# Sheet_1.net
KiCad netlist of a schematic drawn in EasyEDA
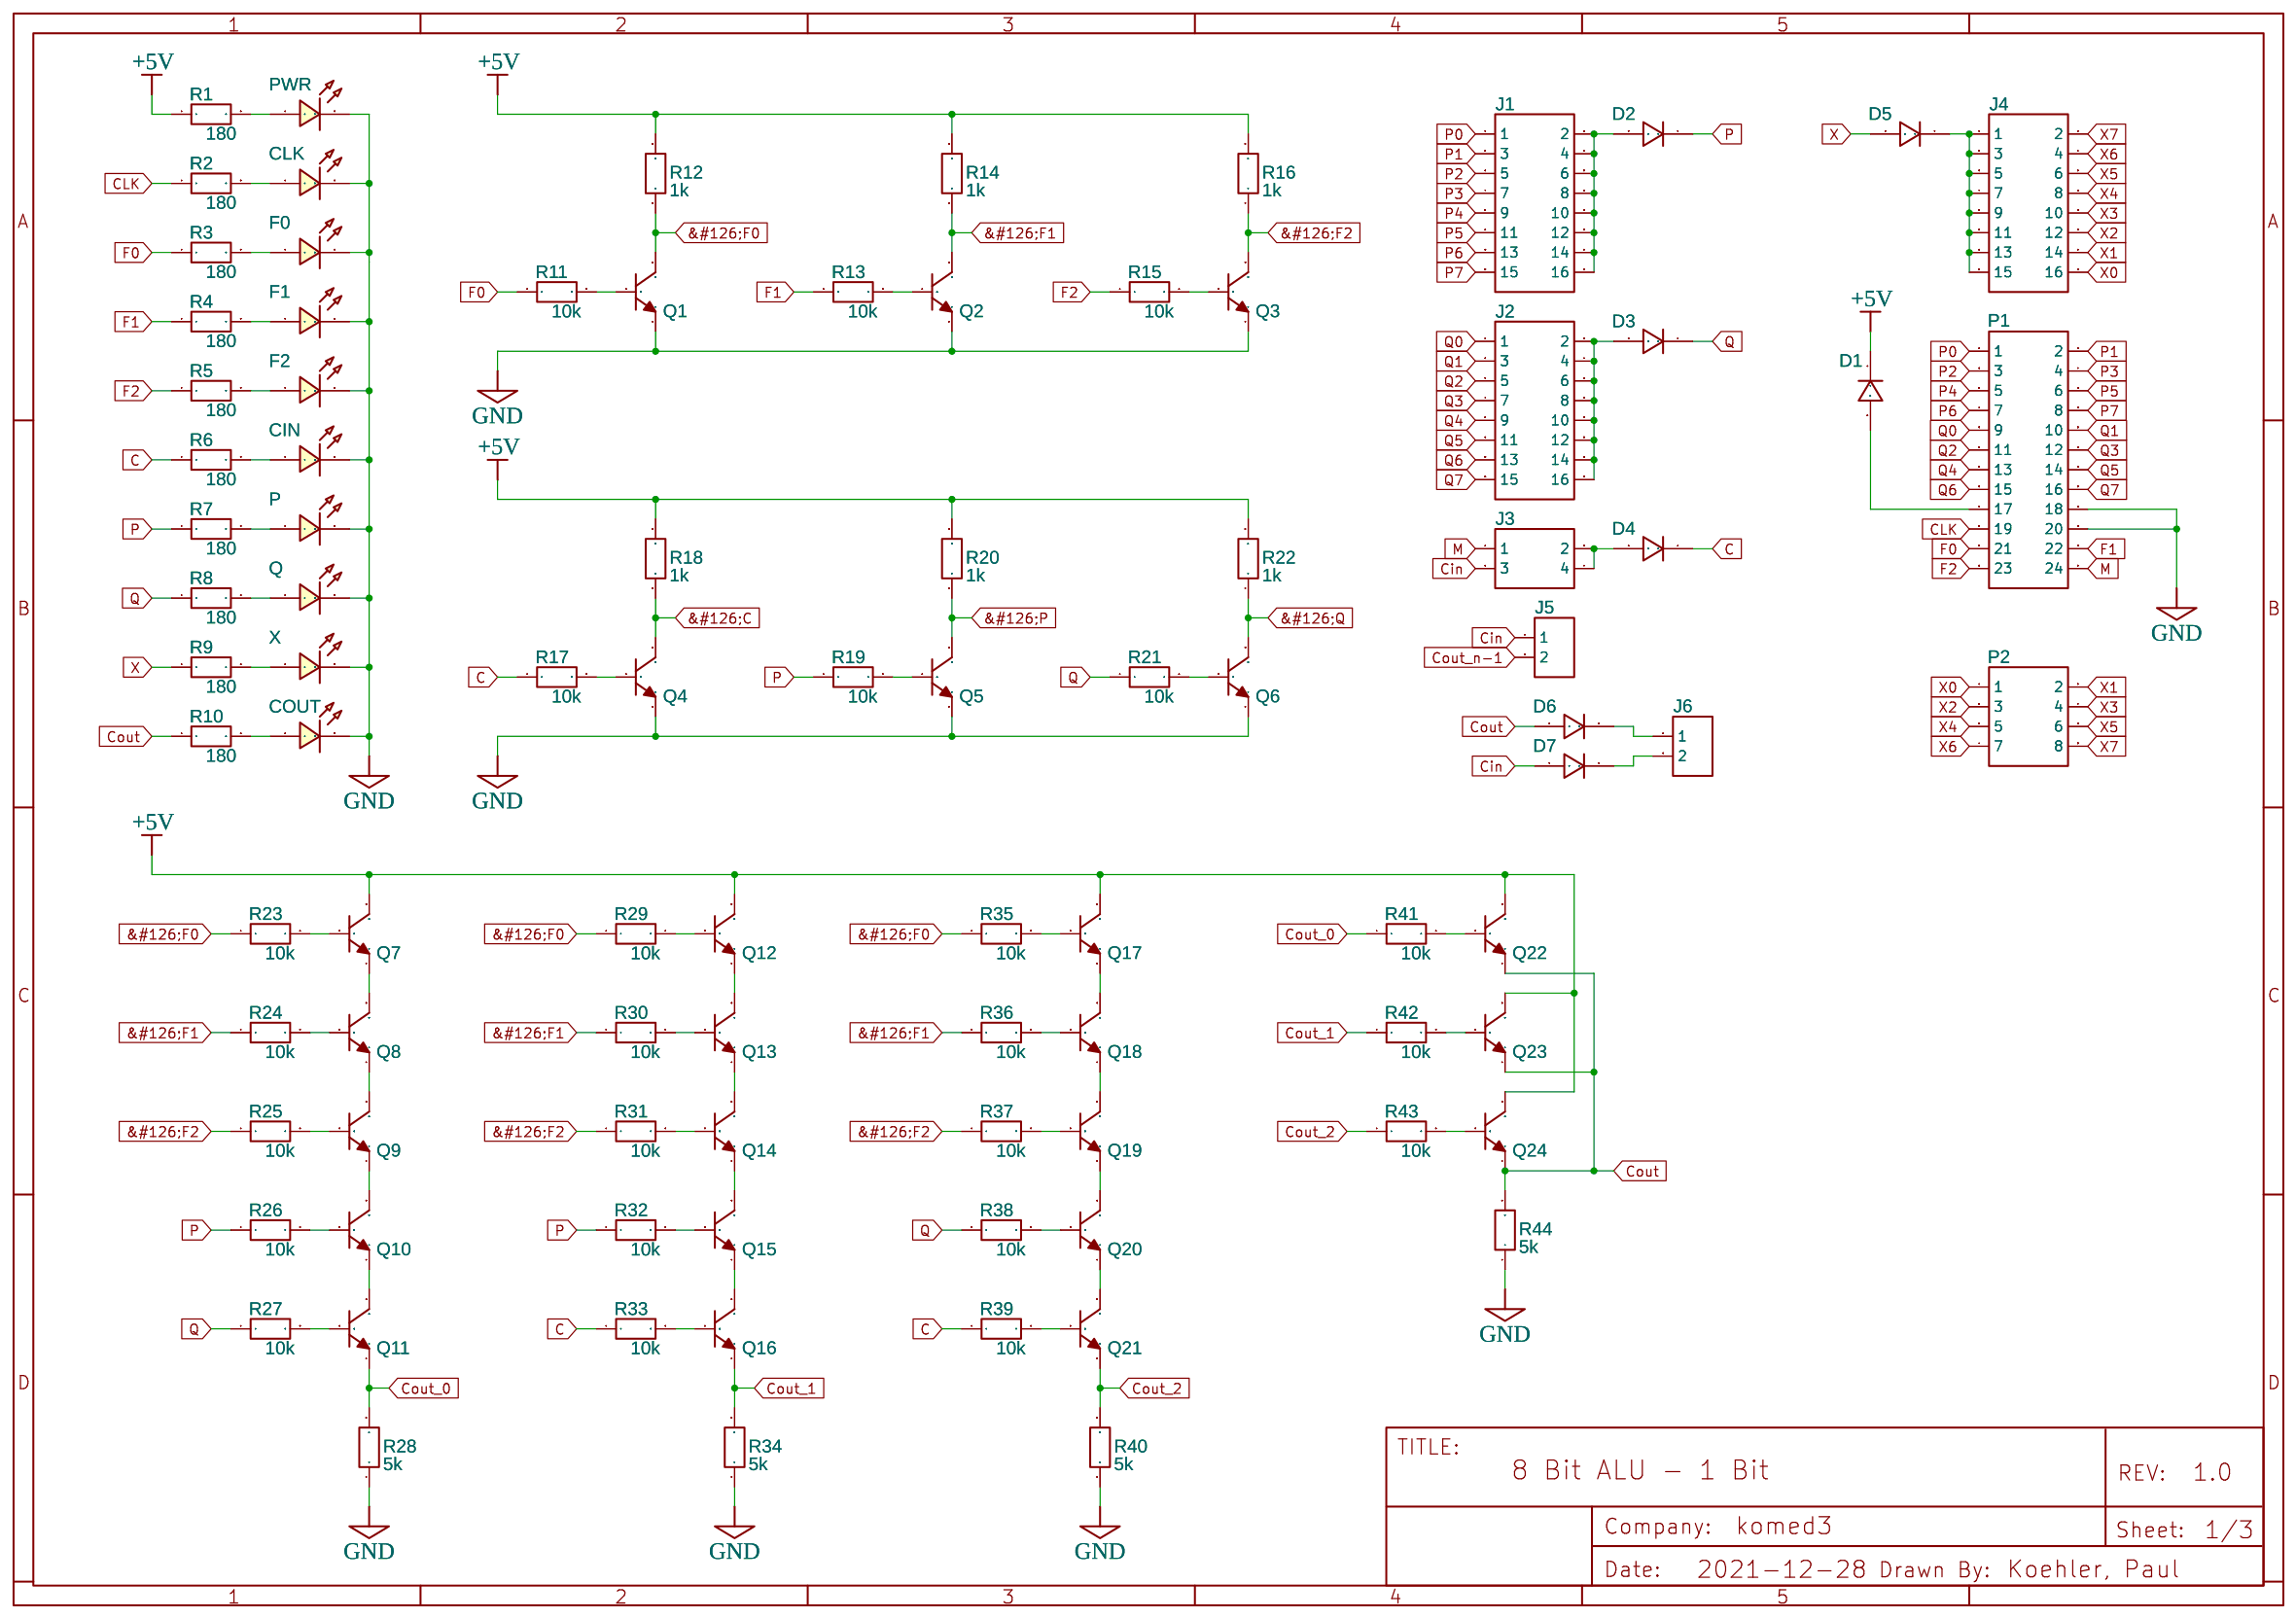
[diagram p0: schematic sheet]

(export (version "E")
  (design (tool "Eeschema 10.0.6"))
  (components
    (comp (ref "CIN")
      (value "LED-TH-5mm_R")
      (fields
        (field (name "BOM_Manufacturer Part") "333-2SURD/S530-A3")
        (field (name "BOM_Supplier Part") "C87271")
      )
      (libsource (lib "") (part "LED-TH-5mm_R_7"))
    )
    (comp (ref "CLK")
      (value "LED-TH-5mm_R")
      (fields
        (field (name "BOM_Manufacturer Part") "333-2SURD/S530-A3")
        (field (name "BOM_Supplier Part") "C87271")
      )
      (libsource (lib "") (part "LED-TH-5mm_R_3"))
    )
    (comp (ref "COUT")
      (value "LED-TH-5mm_R")
      (fields
        (field (name "BOM_Manufacturer Part") "333-2SURD/S530-A3")
        (field (name "BOM_Supplier Part") "C87271")
      )
      (libsource (lib "") (part "LED-TH-5mm_R_5"))
    )
    (comp (ref "D1")
      (value "1N4007")
      (fields (field (name "BOM_Supplier Part") "C106903"))
      (libsource (lib "") (part "1N4007_1"))
    )
    (comp (ref "D2")
      (value "1N4007")
      (fields (field (name "BOM_Supplier Part") "C106903"))
      (libsource (lib "") (part "1N4007"))
    )
    (comp (ref "D3")
      (value "1N4007")
      (fields (field (name "BOM_Supplier Part") "C106903"))
      (libsource (lib "") (part "1N4007"))
    )
    (comp (ref "D4")
      (value "1N4007")
      (fields (field (name "BOM_Supplier Part") "C106903"))
      (libsource (lib "") (part "1N4007"))
    )
    (comp (ref "D5")
      (value "1N4007")
      (fields (field (name "BOM_Supplier Part") "C106903"))
      (libsource (lib "") (part "1N4007"))
    )
    (comp (ref "D6")
      (value "1N4007")
      (fields (field (name "BOM_Supplier Part") "C106903"))
      (libsource (lib "") (part "1N4007"))
    )
    (comp (ref "D7")
      (value "1N4007")
      (fields (field (name "BOM_Supplier Part") "C106903"))
      (libsource (lib "") (part "1N4007"))
    )
    (comp (ref "F0")
      (value "LED-TH-5mm_R")
      (fields
        (field (name "BOM_Manufacturer Part") "333-2SURD/S530-A3")
        (field (name "BOM_Supplier Part") "C87271")
      )
      (libsource (lib "") (part "LED-TH-5mm_R_1"))
    )
    (comp (ref "F1")
      (value "LED-TH-5mm_R")
      (fields
        (field (name "BOM_Manufacturer Part") "333-2SURD/S530-A3")
        (field (name "BOM_Supplier Part") "C87271")
      )
      (libsource (lib "") (part "LED-TH-5mm_R_1"))
    )
    (comp (ref "F2")
      (value "LED-TH-5mm_R")
      (fields
        (field (name "BOM_Manufacturer Part") "333-2SURD/S530-A3")
        (field (name "BOM_Supplier Part") "C87271")
      )
      (libsource (lib "") (part "LED-TH-5mm_R_1"))
    )
    (comp (ref "J1")
      (value "HDR-M-2.54_2x8")
      (fields (field (name "BOM_Supplier Part") "C68234"))
      (libsource (lib "") (part "HDR-M-2.54_2x8"))
    )
    (comp (ref "J2")
      (value "HDR-M-2.54_2x8")
      (fields (field (name "BOM_Supplier Part") "C68234"))
      (libsource (lib "") (part "HDR-M-2.54_2x8"))
    )
    (comp (ref "J3")
      (value "HDR-M-2.54_2x2")
      (fields (field (name "BOM_Supplier Part") "C66690"))
      (libsource (lib "") (part "HDR-M-2.54_2x2"))
    )
    (comp (ref "J4")
      (value "HDR-M-2.54_2x8")
      (fields (field (name "BOM_Supplier Part") "C68234"))
      (libsource (lib "") (part "HDR-M-2.54_2x8"))
    )
    (comp (ref "J5")
      (value "HDR-M-2.54_1x2")
      (fields (field (name "BOM_Supplier Part") "C124375"))
      (libsource (lib "") (part "HDR-M-2.54_1x2"))
    )
    (comp (ref "J6")
      (value "HDR-M-2.54_1x2")
      (fields (field (name "BOM_Supplier Part") "C124375"))
      (libsource (lib "") (part "HDR-M-2.54_1x2"))
    )
    (comp (ref "P")
      (value "LED-TH-5mm_R")
      (fields
        (field (name "BOM_Manufacturer Part") "333-2SURD/S530-A3")
        (field (name "BOM_Supplier Part") "C87271")
      )
      (libsource (lib "") (part "LED-TH-5mm_R_6"))
    )
    (comp (ref "P1")
      (value "HDR-IDC-2.54-2X12P")
      (fields
        (field (name "BOM_Manufacturer Part") "IDC Box 2X12 2.54MM")
        (field (name "BOM_Supplier Part") "C9137")
      )
      (libsource (lib "") (part "HDR-IDC-2.54-2X12P"))
    )
    (comp (ref "P2")
      (value "HDR-IDC-2.54-2X4P")
      (fields
        (field (name "BOM_Manufacturer Part") "IDC Box 2X4 2.54MM")
        (field (name "BOM_Supplier Part") "C9135")
      )
      (libsource (lib "") (part "HDR-IDC-2.54-2X4P"))
    )
    (comp (ref "PWR")
      (value "LED-TH-5mm_R")
      (fields
        (field (name "BOM_Manufacturer Part") "333-2SURD/S530-A3")
        (field (name "BOM_Supplier Part") "C87271")
      )
      (libsource (lib "") (part "LED-TH-5mm_R_4"))
    )
    (comp (ref "Q")
      (value "LED-TH-5mm_R")
      (fields
        (field (name "BOM_Manufacturer Part") "333-2SURD/S530-A3")
        (field (name "BOM_Supplier Part") "C87271")
      )
      (libsource (lib "") (part "LED-TH-5mm_R"))
    )
    (comp (ref "Q1")
      (value "2N3904(TO-92)")
      (fields (field (name "BOM_Manufacturer Part") "2N3904") (field (name "BOM_Supplier Part") "C118538"))
      (libsource (lib "") (part "2N3904(TO-92)"))
    )
    (comp (ref "Q2")
      (value "2N3904(TO-92)")
      (fields (field (name "BOM_Manufacturer Part") "2N3904") (field (name "BOM_Supplier Part") "C118538"))
      (libsource (lib "") (part "2N3904(TO-92)"))
    )
    (comp (ref "Q3")
      (value "2N3904(TO-92)")
      (fields (field (name "BOM_Manufacturer Part") "2N3904") (field (name "BOM_Supplier Part") "C118538"))
      (libsource (lib "") (part "2N3904(TO-92)"))
    )
    (comp (ref "Q4")
      (value "2N3904(TO-92)")
      (fields (field (name "BOM_Manufacturer Part") "2N3904") (field (name "BOM_Supplier Part") "C118538"))
      (libsource (lib "") (part "2N3904(TO-92)"))
    )
    (comp (ref "Q5")
      (value "2N3904(TO-92)")
      (fields (field (name "BOM_Manufacturer Part") "2N3904") (field (name "BOM_Supplier Part") "C118538"))
      (libsource (lib "") (part "2N3904(TO-92)"))
    )
    (comp (ref "Q6")
      (value "2N3904(TO-92)")
      (fields (field (name "BOM_Manufacturer Part") "2N3904") (field (name "BOM_Supplier Part") "C118538"))
      (libsource (lib "") (part "2N3904(TO-92)"))
    )
    (comp (ref "Q7")
      (value "2N3904(TO-92)")
      (fields (field (name "BOM_Manufacturer Part") "2N3904") (field (name "BOM_Supplier Part") "C118538"))
      (libsource (lib "") (part "2N3904(TO-92)"))
    )
    (comp (ref "Q8")
      (value "2N3904(TO-92)")
      (fields (field (name "BOM_Manufacturer Part") "2N3904") (field (name "BOM_Supplier Part") "C118538"))
      (libsource (lib "") (part "2N3904(TO-92)"))
    )
    (comp (ref "Q9")
      (value "2N3904(TO-92)")
      (fields (field (name "BOM_Manufacturer Part") "2N3904") (field (name "BOM_Supplier Part") "C118538"))
      (libsource (lib "") (part "2N3904(TO-92)"))
    )
    (comp (ref "Q10")
      (value "2N3904(TO-92)")
      (fields (field (name "BOM_Manufacturer Part") "2N3904") (field (name "BOM_Supplier Part") "C118538"))
      (libsource (lib "") (part "2N3904(TO-92)"))
    )
    (comp (ref "Q11")
      (value "2N3904(TO-92)")
      (fields (field (name "BOM_Manufacturer Part") "2N3904") (field (name "BOM_Supplier Part") "C118538"))
      (libsource (lib "") (part "2N3904(TO-92)"))
    )
    (comp (ref "Q12")
      (value "2N3904(TO-92)")
      (fields (field (name "BOM_Manufacturer Part") "2N3904") (field (name "BOM_Supplier Part") "C118538"))
      (libsource (lib "") (part "2N3904(TO-92)"))
    )
    (comp (ref "Q13")
      (value "2N3904(TO-92)")
      (fields (field (name "BOM_Manufacturer Part") "2N3904") (field (name "BOM_Supplier Part") "C118538"))
      (libsource (lib "") (part "2N3904(TO-92)"))
    )
    (comp (ref "Q14")
      (value "2N3904(TO-92)")
      (fields (field (name "BOM_Manufacturer Part") "2N3904") (field (name "BOM_Supplier Part") "C118538"))
      (libsource (lib "") (part "2N3904(TO-92)"))
    )
    (comp (ref "Q15")
      (value "2N3904(TO-92)")
      (fields (field (name "BOM_Manufacturer Part") "2N3904") (field (name "BOM_Supplier Part") "C118538"))
      (libsource (lib "") (part "2N3904(TO-92)"))
    )
    (comp (ref "Q16")
      (value "2N3904(TO-92)")
      (fields (field (name "BOM_Manufacturer Part") "2N3904") (field (name "BOM_Supplier Part") "C118538"))
      (libsource (lib "") (part "2N3904(TO-92)"))
    )
    (comp (ref "Q17")
      (value "2N3904(TO-92)")
      (fields (field (name "BOM_Manufacturer Part") "2N3904") (field (name "BOM_Supplier Part") "C118538"))
      (libsource (lib "") (part "2N3904(TO-92)"))
    )
    (comp (ref "Q18")
      (value "2N3904(TO-92)")
      (fields (field (name "BOM_Manufacturer Part") "2N3904") (field (name "BOM_Supplier Part") "C118538"))
      (libsource (lib "") (part "2N3904(TO-92)"))
    )
    (comp (ref "Q19")
      (value "2N3904(TO-92)")
      (fields (field (name "BOM_Manufacturer Part") "2N3904") (field (name "BOM_Supplier Part") "C118538"))
      (libsource (lib "") (part "2N3904(TO-92)"))
    )
    (comp (ref "Q20")
      (value "2N3904(TO-92)")
      (fields (field (name "BOM_Manufacturer Part") "2N3904") (field (name "BOM_Supplier Part") "C118538"))
      (libsource (lib "") (part "2N3904(TO-92)"))
    )
    (comp (ref "Q21")
      (value "2N3904(TO-92)")
      (fields (field (name "BOM_Manufacturer Part") "2N3904") (field (name "BOM_Supplier Part") "C118538"))
      (libsource (lib "") (part "2N3904(TO-92)"))
    )
    (comp (ref "Q22")
      (value "2N3904(TO-92)")
      (fields (field (name "BOM_Manufacturer Part") "2N3904") (field (name "BOM_Supplier Part") "C118538"))
      (libsource (lib "") (part "2N3904(TO-92)"))
    )
    (comp (ref "Q23")
      (value "2N3904(TO-92)")
      (fields (field (name "BOM_Manufacturer Part") "2N3904") (field (name "BOM_Supplier Part") "C118538"))
      (libsource (lib "") (part "2N3904(TO-92)"))
    )
    (comp (ref "Q24")
      (value "2N3904(TO-92)")
      (fields (field (name "BOM_Manufacturer Part") "2N3904") (field (name "BOM_Supplier Part") "C118538"))
      (libsource (lib "") (part "2N3904(TO-92)"))
    )
    (comp (ref "R1") (value "180") (libsource (lib "") (part "R_AXIAL-0.3_EU")))
    (comp (ref "R2") (value "180") (libsource (lib "") (part "R_AXIAL-0.3_EU")))
    (comp (ref "R3") (value "180") (libsource (lib "") (part "R_AXIAL-0.3_EU")))
    (comp (ref "R4") (value "180") (libsource (lib "") (part "R_AXIAL-0.3_EU")))
    (comp (ref "R5") (value "180") (libsource (lib "") (part "R_AXIAL-0.3_EU")))
    (comp (ref "R6") (value "180") (libsource (lib "") (part "R_AXIAL-0.3_EU")))
    (comp (ref "R7") (value "180") (libsource (lib "") (part "R_AXIAL-0.3_EU")))
    (comp (ref "R8") (value "180") (libsource (lib "") (part "R_AXIAL-0.3_EU")))
    (comp (ref "R9") (value "180") (libsource (lib "") (part "R_AXIAL-0.3_EU")))
    (comp (ref "R10") (value "180") (libsource (lib "") (part "R_AXIAL-0.3_EU")))
    (comp (ref "R11") (value "10k") (libsource (lib "") (part "R_AXIAL-0.3_EU")))
    (comp (ref "R12") (value "1k") (libsource (lib "") (part "R_AXIAL-0.3_EU_1")))
    (comp (ref "R13") (value "10k") (libsource (lib "") (part "R_AXIAL-0.3_EU")))
    (comp (ref "R14") (value "1k") (libsource (lib "") (part "R_AXIAL-0.3_EU_1")))
    (comp (ref "R15") (value "10k") (libsource (lib "") (part "R_AXIAL-0.3_EU")))
    (comp (ref "R16") (value "1k") (libsource (lib "") (part "R_AXIAL-0.3_EU_1")))
    (comp (ref "R17") (value "10k") (libsource (lib "") (part "R_AXIAL-0.3_EU")))
    (comp (ref "R18") (value "1k") (libsource (lib "") (part "R_AXIAL-0.3_EU_1")))
    (comp (ref "R19") (value "10k") (libsource (lib "") (part "R_AXIAL-0.3_EU")))
    (comp (ref "R20") (value "1k") (libsource (lib "") (part "R_AXIAL-0.3_EU_1")))
    (comp (ref "R21") (value "10k") (libsource (lib "") (part "R_AXIAL-0.3_EU")))
    (comp (ref "R22") (value "1k") (libsource (lib "") (part "R_AXIAL-0.3_EU_1")))
    (comp (ref "R23") (value "10k") (libsource (lib "") (part "R_AXIAL-0.3_EU")))
    (comp (ref "R24") (value "10k") (libsource (lib "") (part "R_AXIAL-0.3_EU")))
    (comp (ref "R25") (value "10k") (libsource (lib "") (part "R_AXIAL-0.3_EU")))
    (comp (ref "R26") (value "10k") (libsource (lib "") (part "R_AXIAL-0.3_EU")))
    (comp (ref "R27") (value "10k") (libsource (lib "") (part "R_AXIAL-0.3_EU")))
    (comp (ref "R28") (value "5k") (libsource (lib "") (part "R_AXIAL-0.3_EU_1")))
    (comp (ref "R29") (value "10k") (libsource (lib "") (part "R_AXIAL-0.3_EU")))
    (comp (ref "R30") (value "10k") (libsource (lib "") (part "R_AXIAL-0.3_EU")))
    (comp (ref "R31") (value "10k") (libsource (lib "") (part "R_AXIAL-0.3_EU")))
    (comp (ref "R32") (value "10k") (libsource (lib "") (part "R_AXIAL-0.3_EU")))
    (comp (ref "R33") (value "10k") (libsource (lib "") (part "R_AXIAL-0.3_EU")))
    (comp (ref "R34") (value "5k") (libsource (lib "") (part "R_AXIAL-0.3_EU_1")))
    (comp (ref "R35") (value "10k") (libsource (lib "") (part "R_AXIAL-0.3_EU")))
    (comp (ref "R36") (value "10k") (libsource (lib "") (part "R_AXIAL-0.3_EU")))
    (comp (ref "R37") (value "10k") (libsource (lib "") (part "R_AXIAL-0.3_EU")))
    (comp (ref "R38") (value "10k") (libsource (lib "") (part "R_AXIAL-0.3_EU")))
    (comp (ref "R39") (value "10k") (libsource (lib "") (part "R_AXIAL-0.3_EU")))
    (comp (ref "R40") (value "5k") (libsource (lib "") (part "R_AXIAL-0.3_EU_1")))
    (comp (ref "R41") (value "10k") (libsource (lib "") (part "R_AXIAL-0.3_EU")))
    (comp (ref "R42") (value "10k") (libsource (lib "") (part "R_AXIAL-0.3_EU")))
    (comp (ref "R43") (value "10k") (libsource (lib "") (part "R_AXIAL-0.3_EU")))
    (comp (ref "R44") (value "5k") (libsource (lib "") (part "R_AXIAL-0.3_EU_1")))
    (comp (ref "X")
      (value "LED-TH-5mm_R")
      (fields
        (field (name "BOM_Manufacturer Part") "333-2SURD/S530-A3")
        (field (name "BOM_Supplier Part") "C87271")
      )
      (libsource (lib "") (part "LED-TH-5mm_R_2"))
    )
  )
  (nets
    (net (code "1") (name "&#126;C") (class "Default")
      (node (ref "Q4") (pin "3") (pinfunction "C_3") (pintype "unspecified"))
      (node (ref "R18") (pin "1") (pinfunction "1_1") (pintype "unspecified"))
    )
    (net (code "2") (name "&#126;F0") (class "Default")
      (node (ref "Q1") (pin "3") (pinfunction "C_3") (pintype "unspecified"))
      (node (ref "R12") (pin "1") (pinfunction "1_1") (pintype "unspecified"))
      (node (ref "R23") (pin "1") (pinfunction "1_1") (pintype "unspecified"))
      (node (ref "R29") (pin "1") (pinfunction "1_1") (pintype "unspecified"))
      (node (ref "R35") (pin "1") (pinfunction "1_1") (pintype "unspecified"))
    )
    (net (code "3") (name "&#126;F1") (class "Default")
      (node (ref "Q2") (pin "3") (pinfunction "C_3") (pintype "unspecified"))
      (node (ref "R14") (pin "1") (pinfunction "1_1") (pintype "unspecified"))
      (node (ref "R24") (pin "1") (pinfunction "1_1") (pintype "unspecified"))
      (node (ref "R30") (pin "1") (pinfunction "1_1") (pintype "unspecified"))
      (node (ref "R36") (pin "1") (pinfunction "1_1") (pintype "unspecified"))
    )
    (net (code "4") (name "&#126;F2") (class "Default")
      (node (ref "Q3") (pin "3") (pinfunction "C_3") (pintype "unspecified"))
      (node (ref "R16") (pin "1") (pinfunction "1_1") (pintype "unspecified"))
      (node (ref "R25") (pin "1") (pinfunction "1_1") (pintype "unspecified"))
      (node (ref "R31") (pin "1") (pinfunction "1_1") (pintype "unspecified"))
      (node (ref "R37") (pin "1") (pinfunction "1_1") (pintype "unspecified"))
    )
    (net (code "5") (name "&#126;P") (class "Default")
      (node (ref "Q5") (pin "3") (pinfunction "C_3") (pintype "unspecified"))
      (node (ref "R20") (pin "1") (pinfunction "1_1") (pintype "unspecified"))
    )
    (net (code "6") (name "&#126;Q") (class "Default")
      (node (ref "Q6") (pin "3") (pinfunction "C_3") (pintype "unspecified"))
      (node (ref "R22") (pin "1") (pinfunction "1_1") (pintype "unspecified"))
    )
    (net (code "7") (name "+5V") (class "Default")
      (node (ref "D1") (pin "1") (pinfunction "1_1") (pintype "unspecified"))
      (node (ref "Q12") (pin "3") (pinfunction "C_3") (pintype "unspecified"))
      (node (ref "Q17") (pin "3") (pinfunction "C_3") (pintype "unspecified"))
      (node (ref "Q22") (pin "3") (pinfunction "C_3") (pintype "unspecified"))
      (node (ref "Q23") (pin "3") (pinfunction "C_3") (pintype "unspecified"))
      (node (ref "Q24") (pin "3") (pinfunction "C_3") (pintype "unspecified"))
      (node (ref "Q7") (pin "3") (pinfunction "C_3") (pintype "unspecified"))
      (node (ref "R1") (pin "1") (pinfunction "1_1") (pintype "unspecified"))
      (node (ref "R12") (pin "2") (pinfunction "2_2") (pintype "unspecified"))
      (node (ref "R14") (pin "2") (pinfunction "2_2") (pintype "unspecified"))
      (node (ref "R16") (pin "2") (pinfunction "2_2") (pintype "unspecified"))
      (node (ref "R18") (pin "2") (pinfunction "2_2") (pintype "unspecified"))
      (node (ref "R20") (pin "2") (pinfunction "2_2") (pintype "unspecified"))
      (node (ref "R22") (pin "2") (pinfunction "2_2") (pintype "unspecified"))
    )
    (net (code "8") (name "C") (class "Default")
      (node (ref "D4") (pin "1") (pinfunction "1_1") (pintype "unspecified"))
      (node (ref "R17") (pin "1") (pinfunction "1_1") (pintype "unspecified"))
      (node (ref "R33") (pin "1") (pinfunction "1_1") (pintype "unspecified"))
      (node (ref "R39") (pin "1") (pinfunction "1_1") (pintype "unspecified"))
      (node (ref "R6") (pin "1") (pinfunction "1_1") (pintype "unspecified"))
    )
    (net (code "9") (name "CLK") (class "Default")
      (node (ref "P1") (pin "19") (pinfunction "19_19") (pintype "unspecified"))
      (node (ref "R2") (pin "1") (pinfunction "1_1") (pintype "unspecified"))
    )
    (net (code "10") (name "Cin") (class "Default")
      (node (ref "D7") (pin "2") (pinfunction "2_2") (pintype "unspecified"))
      (node (ref "J3") (pin "3") (pinfunction "3_3") (pintype "input"))
      (node (ref "J5") (pin "1") (pinfunction "1_1") (pintype "unspecified"))
    )
    (net (code "11") (name "Cout") (class "Default")
      (node (ref "D6") (pin "2") (pinfunction "2_2") (pintype "unspecified"))
      (node (ref "Q22") (pin "1") (pinfunction "E_1") (pintype "unspecified"))
      (node (ref "Q23") (pin "1") (pinfunction "E_1") (pintype "unspecified"))
      (node (ref "Q24") (pin "1") (pinfunction "E_1") (pintype "unspecified"))
      (node (ref "R10") (pin "1") (pinfunction "1_1") (pintype "unspecified"))
      (node (ref "R44") (pin "2") (pinfunction "2_2") (pintype "unspecified"))
    )
    (net (code "12") (name "Cout_0") (class "Default")
      (node (ref "Q11") (pin "1") (pinfunction "E_1") (pintype "unspecified"))
      (node (ref "R28") (pin "2") (pinfunction "2_2") (pintype "unspecified"))
      (node (ref "R41") (pin "1") (pinfunction "1_1") (pintype "unspecified"))
    )
    (net (code "13") (name "Cout_1") (class "Default")
      (node (ref "Q16") (pin "1") (pinfunction "E_1") (pintype "unspecified"))
      (node (ref "R34") (pin "2") (pinfunction "2_2") (pintype "unspecified"))
      (node (ref "R42") (pin "1") (pinfunction "1_1") (pintype "unspecified"))
    )
    (net (code "14") (name "Cout_2") (class "Default")
      (node (ref "Q21") (pin "1") (pinfunction "E_1") (pintype "unspecified"))
      (node (ref "R40") (pin "2") (pinfunction "2_2") (pintype "unspecified"))
      (node (ref "R43") (pin "1") (pinfunction "1_1") (pintype "unspecified"))
    )
    (net (code "15") (name "Cout_n-1") (class "Default")
      (node (ref "J5") (pin "2") (pinfunction "2_2") (pintype "unspecified"))
    )
    (net (code "16") (name "F0") (class "Default")
      (node (ref "P1") (pin "21") (pinfunction "21_21") (pintype "unspecified"))
      (node (ref "R11") (pin "1") (pinfunction "1_1") (pintype "unspecified"))
      (node (ref "R3") (pin "1") (pinfunction "1_1") (pintype "unspecified"))
    )
    (net (code "17") (name "F1") (class "Default")
      (node (ref "P1") (pin "22") (pinfunction "22_22") (pintype "unspecified"))
      (node (ref "R13") (pin "1") (pinfunction "1_1") (pintype "unspecified"))
      (node (ref "R4") (pin "1") (pinfunction "1_1") (pintype "unspecified"))
    )
    (net (code "18") (name "F2") (class "Default")
      (node (ref "P1") (pin "23") (pinfunction "23_23") (pintype "unspecified"))
      (node (ref "R15") (pin "1") (pinfunction "1_1") (pintype "unspecified"))
      (node (ref "R5") (pin "1") (pinfunction "1_1") (pintype "unspecified"))
    )
    (net (code "19") (name "GND") (class "Default")
      (node (ref "CIN") (pin "2") (pinfunction "2_2") (pintype "unspecified"))
      (node (ref "CLK") (pin "2") (pinfunction "2_2") (pintype "unspecified"))
      (node (ref "COUT") (pin "2") (pinfunction "2_2") (pintype "unspecified"))
      (node (ref "F0") (pin "2") (pinfunction "2_2") (pintype "unspecified"))
      (node (ref "F1") (pin "2") (pinfunction "2_2") (pintype "unspecified"))
      (node (ref "F2") (pin "2") (pinfunction "2_2") (pintype "unspecified"))
      (node (ref "P") (pin "2") (pinfunction "2_2") (pintype "unspecified"))
      (node (ref "P1") (pin "18") (pinfunction "18_18") (pintype "unspecified"))
      (node (ref "P1") (pin "20") (pinfunction "20_20") (pintype "unspecified"))
      (node (ref "PWR") (pin "2") (pinfunction "2_2") (pintype "unspecified"))
      (node (ref "Q") (pin "2") (pinfunction "2_2") (pintype "unspecified"))
      (node (ref "Q1") (pin "1") (pinfunction "E_1") (pintype "unspecified"))
      (node (ref "Q2") (pin "1") (pinfunction "E_1") (pintype "unspecified"))
      (node (ref "Q3") (pin "1") (pinfunction "E_1") (pintype "unspecified"))
      (node (ref "Q4") (pin "1") (pinfunction "E_1") (pintype "unspecified"))
      (node (ref "Q5") (pin "1") (pinfunction "E_1") (pintype "unspecified"))
      (node (ref "Q6") (pin "1") (pinfunction "E_1") (pintype "unspecified"))
      (node (ref "R28") (pin "1") (pinfunction "1_1") (pintype "unspecified"))
      (node (ref "R34") (pin "1") (pinfunction "1_1") (pintype "unspecified"))
      (node (ref "R40") (pin "1") (pinfunction "1_1") (pintype "unspecified"))
      (node (ref "R44") (pin "1") (pinfunction "1_1") (pintype "unspecified"))
      (node (ref "X") (pin "2") (pinfunction "2_2") (pintype "unspecified"))
    )
    (net (code "20") (name "M") (class "Default")
      (node (ref "J3") (pin "1") (pinfunction "1_1") (pintype "input"))
      (node (ref "P1") (pin "24") (pinfunction "24_24") (pintype "unspecified"))
    )
    (net (code "21") (name "Net-(CIN-Pad1)") (class "Default")
      (node (ref "CIN") (pin "1") (pinfunction "1_1") (pintype "unspecified"))
      (node (ref "R6") (pin "2") (pinfunction "2_2") (pintype "unspecified"))
    )
    (net (code "22") (name "Net-(CLK-Pad1)") (class "Default")
      (node (ref "CLK") (pin "1") (pinfunction "1_1") (pintype "unspecified"))
      (node (ref "R2") (pin "2") (pinfunction "2_2") (pintype "unspecified"))
    )
    (net (code "23") (name "Net-(COUT-Pad1)") (class "Default")
      (node (ref "COUT") (pin "1") (pinfunction "1_1") (pintype "unspecified"))
      (node (ref "R10") (pin "2") (pinfunction "2_2") (pintype "unspecified"))
    )
    (net (code "24") (name "Net-(D1-Pad2)") (class "Default")
      (node (ref "D1") (pin "2") (pinfunction "2_2") (pintype "unspecified"))
      (node (ref "P1") (pin "17") (pinfunction "17_17") (pintype "unspecified"))
    )
    (net (code "25") (name "Net-(D2-Pad2)") (class "Default")
      (node (ref "D2") (pin "2") (pinfunction "2_2") (pintype "unspecified"))
      (node (ref "J1") (pin "10") (pinfunction "10_10") (pintype "input"))
      (node (ref "J1") (pin "12") (pinfunction "12_12") (pintype "input"))
      (node (ref "J1") (pin "14") (pinfunction "14_14") (pintype "input"))
      (node (ref "J1") (pin "16") (pinfunction "16_16") (pintype "input"))
      (node (ref "J1") (pin "2") (pinfunction "2_2") (pintype "input"))
      (node (ref "J1") (pin "4") (pinfunction "4_4") (pintype "input"))
      (node (ref "J1") (pin "6") (pinfunction "6_6") (pintype "input"))
      (node (ref "J1") (pin "8") (pinfunction "8_8") (pintype "input"))
    )
    (net (code "26") (name "Net-(D3-Pad2)") (class "Default")
      (node (ref "D3") (pin "2") (pinfunction "2_2") (pintype "unspecified"))
      (node (ref "J2") (pin "10") (pinfunction "10_10") (pintype "input"))
      (node (ref "J2") (pin "12") (pinfunction "12_12") (pintype "input"))
      (node (ref "J2") (pin "14") (pinfunction "14_14") (pintype "input"))
      (node (ref "J2") (pin "16") (pinfunction "16_16") (pintype "input"))
      (node (ref "J2") (pin "2") (pinfunction "2_2") (pintype "input"))
      (node (ref "J2") (pin "4") (pinfunction "4_4") (pintype "input"))
      (node (ref "J2") (pin "6") (pinfunction "6_6") (pintype "input"))
      (node (ref "J2") (pin "8") (pinfunction "8_8") (pintype "input"))
    )
    (net (code "27") (name "Net-(D4-Pad2)") (class "Default")
      (node (ref "D4") (pin "2") (pinfunction "2_2") (pintype "unspecified"))
      (node (ref "J3") (pin "2") (pinfunction "2_2") (pintype "input"))
      (node (ref "J3") (pin "4") (pinfunction "4_4") (pintype "input"))
    )
    (net (code "28") (name "Net-(D5-Pad1)") (class "Default")
      (node (ref "D5") (pin "1") (pinfunction "1_1") (pintype "unspecified"))
      (node (ref "J4") (pin "1") (pinfunction "1_1") (pintype "input"))
      (node (ref "J4") (pin "11") (pinfunction "11_11") (pintype "input"))
      (node (ref "J4") (pin "13") (pinfunction "13_13") (pintype "input"))
      (node (ref "J4") (pin "15") (pinfunction "15_15") (pintype "input"))
      (node (ref "J4") (pin "3") (pinfunction "3_3") (pintype "input"))
      (node (ref "J4") (pin "5") (pinfunction "5_5") (pintype "input"))
      (node (ref "J4") (pin "7") (pinfunction "7_7") (pintype "input"))
      (node (ref "J4") (pin "9") (pinfunction "9_9") (pintype "input"))
    )
    (net (code "29") (name "Net-(D6-Pad1)") (class "Default")
      (node (ref "D6") (pin "1") (pinfunction "1_1") (pintype "unspecified"))
      (node (ref "J6") (pin "1") (pinfunction "1_1") (pintype "unspecified"))
    )
    (net (code "30") (name "Net-(D7-Pad1)") (class "Default")
      (node (ref "D7") (pin "1") (pinfunction "1_1") (pintype "unspecified"))
      (node (ref "J6") (pin "2") (pinfunction "2_2") (pintype "unspecified"))
    )
    (net (code "31") (name "Net-(F0-Pad1)") (class "Default")
      (node (ref "F0") (pin "1") (pinfunction "1_1") (pintype "unspecified"))
      (node (ref "R3") (pin "2") (pinfunction "2_2") (pintype "unspecified"))
    )
    (net (code "32") (name "Net-(F1-Pad1)") (class "Default")
      (node (ref "F1") (pin "1") (pinfunction "1_1") (pintype "unspecified"))
      (node (ref "R4") (pin "2") (pinfunction "2_2") (pintype "unspecified"))
    )
    (net (code "33") (name "Net-(F2-Pad1)") (class "Default")
      (node (ref "F2") (pin "1") (pinfunction "1_1") (pintype "unspecified"))
      (node (ref "R5") (pin "2") (pinfunction "2_2") (pintype "unspecified"))
    )
    (net (code "34") (name "Net-(P-Pad1)") (class "Default")
      (node (ref "P") (pin "1") (pinfunction "1_1") (pintype "unspecified"))
      (node (ref "R7") (pin "2") (pinfunction "2_2") (pintype "unspecified"))
    )
    (net (code "35") (name "Net-(PWR-Pad1)") (class "Default")
      (node (ref "PWR") (pin "1") (pinfunction "1_1") (pintype "unspecified"))
      (node (ref "R1") (pin "2") (pinfunction "2_2") (pintype "unspecified"))
    )
    (net (code "36") (name "Net-(Q-Pad1)") (class "Default")
      (node (ref "Q") (pin "1") (pinfunction "1_1") (pintype "unspecified"))
      (node (ref "R8") (pin "2") (pinfunction "2_2") (pintype "unspecified"))
    )
    (net (code "37") (name "Net-(Q1-B)") (class "Default")
      (node (ref "Q1") (pin "2") (pinfunction "B_2") (pintype "unspecified"))
      (node (ref "R11") (pin "2") (pinfunction "2_2") (pintype "unspecified"))
    )
    (net (code "38") (name "Net-(Q2-B)") (class "Default")
      (node (ref "Q2") (pin "2") (pinfunction "B_2") (pintype "unspecified"))
      (node (ref "R13") (pin "2") (pinfunction "2_2") (pintype "unspecified"))
    )
    (net (code "39") (name "Net-(Q3-B)") (class "Default")
      (node (ref "Q3") (pin "2") (pinfunction "B_2") (pintype "unspecified"))
      (node (ref "R15") (pin "2") (pinfunction "2_2") (pintype "unspecified"))
    )
    (net (code "40") (name "Net-(Q4-B)") (class "Default")
      (node (ref "Q4") (pin "2") (pinfunction "B_2") (pintype "unspecified"))
      (node (ref "R17") (pin "2") (pinfunction "2_2") (pintype "unspecified"))
    )
    (net (code "41") (name "Net-(Q5-B)") (class "Default")
      (node (ref "Q5") (pin "2") (pinfunction "B_2") (pintype "unspecified"))
      (node (ref "R19") (pin "2") (pinfunction "2_2") (pintype "unspecified"))
    )
    (net (code "42") (name "Net-(Q6-B)") (class "Default")
      (node (ref "Q6") (pin "2") (pinfunction "B_2") (pintype "unspecified"))
      (node (ref "R21") (pin "2") (pinfunction "2_2") (pintype "unspecified"))
    )
    (net (code "43") (name "Net-(Q7-B)") (class "Default")
      (node (ref "Q7") (pin "2") (pinfunction "B_2") (pintype "unspecified"))
      (node (ref "R23") (pin "2") (pinfunction "2_2") (pintype "unspecified"))
    )
    (net (code "44") (name "Net-(Q7-E)") (class "Default")
      (node (ref "Q7") (pin "1") (pinfunction "E_1") (pintype "unspecified"))
      (node (ref "Q8") (pin "3") (pinfunction "C_3") (pintype "unspecified"))
    )
    (net (code "45") (name "Net-(Q8-B)") (class "Default")
      (node (ref "Q8") (pin "2") (pinfunction "B_2") (pintype "unspecified"))
      (node (ref "R24") (pin "2") (pinfunction "2_2") (pintype "unspecified"))
    )
    (net (code "46") (name "Net-(Q8-E)") (class "Default")
      (node (ref "Q8") (pin "1") (pinfunction "E_1") (pintype "unspecified"))
      (node (ref "Q9") (pin "3") (pinfunction "C_3") (pintype "unspecified"))
    )
    (net (code "47") (name "Net-(Q9-B)") (class "Default")
      (node (ref "Q9") (pin "2") (pinfunction "B_2") (pintype "unspecified"))
      (node (ref "R25") (pin "2") (pinfunction "2_2") (pintype "unspecified"))
    )
    (net (code "48") (name "Net-(Q10-B)") (class "Default")
      (node (ref "Q10") (pin "2") (pinfunction "B_2") (pintype "unspecified"))
      (node (ref "R26") (pin "2") (pinfunction "2_2") (pintype "unspecified"))
    )
    (net (code "49") (name "Net-(Q10-C)") (class "Default")
      (node (ref "Q10") (pin "3") (pinfunction "C_3") (pintype "unspecified"))
      (node (ref "Q9") (pin "1") (pinfunction "E_1") (pintype "unspecified"))
    )
    (net (code "50") (name "Net-(Q10-E)") (class "Default")
      (node (ref "Q10") (pin "1") (pinfunction "E_1") (pintype "unspecified"))
      (node (ref "Q11") (pin "3") (pinfunction "C_3") (pintype "unspecified"))
    )
    (net (code "51") (name "Net-(Q11-B)") (class "Default")
      (node (ref "Q11") (pin "2") (pinfunction "B_2") (pintype "unspecified"))
      (node (ref "R27") (pin "2") (pinfunction "2_2") (pintype "unspecified"))
    )
    (net (code "52") (name "Net-(Q12-B)") (class "Default")
      (node (ref "Q12") (pin "2") (pinfunction "B_2") (pintype "unspecified"))
      (node (ref "R29") (pin "2") (pinfunction "2_2") (pintype "unspecified"))
    )
    (net (code "53") (name "Net-(Q12-E)") (class "Default")
      (node (ref "Q12") (pin "1") (pinfunction "E_1") (pintype "unspecified"))
      (node (ref "Q13") (pin "3") (pinfunction "C_3") (pintype "unspecified"))
    )
    (net (code "54") (name "Net-(Q13-B)") (class "Default")
      (node (ref "Q13") (pin "2") (pinfunction "B_2") (pintype "unspecified"))
      (node (ref "R30") (pin "2") (pinfunction "2_2") (pintype "unspecified"))
    )
    (net (code "55") (name "Net-(Q13-E)") (class "Default")
      (node (ref "Q13") (pin "1") (pinfunction "E_1") (pintype "unspecified"))
      (node (ref "Q14") (pin "3") (pinfunction "C_3") (pintype "unspecified"))
    )
    (net (code "56") (name "Net-(Q14-B)") (class "Default")
      (node (ref "Q14") (pin "2") (pinfunction "B_2") (pintype "unspecified"))
      (node (ref "R31") (pin "2") (pinfunction "2_2") (pintype "unspecified"))
    )
    (net (code "57") (name "Net-(Q14-E)") (class "Default")
      (node (ref "Q14") (pin "1") (pinfunction "E_1") (pintype "unspecified"))
      (node (ref "Q15") (pin "3") (pinfunction "C_3") (pintype "unspecified"))
    )
    (net (code "58") (name "Net-(Q15-B)") (class "Default")
      (node (ref "Q15") (pin "2") (pinfunction "B_2") (pintype "unspecified"))
      (node (ref "R32") (pin "2") (pinfunction "2_2") (pintype "unspecified"))
    )
    (net (code "59") (name "Net-(Q15-E)") (class "Default")
      (node (ref "Q15") (pin "1") (pinfunction "E_1") (pintype "unspecified"))
      (node (ref "Q16") (pin "3") (pinfunction "C_3") (pintype "unspecified"))
    )
    (net (code "60") (name "Net-(Q16-B)") (class "Default")
      (node (ref "Q16") (pin "2") (pinfunction "B_2") (pintype "unspecified"))
      (node (ref "R33") (pin "2") (pinfunction "2_2") (pintype "unspecified"))
    )
    (net (code "61") (name "Net-(Q17-B)") (class "Default")
      (node (ref "Q17") (pin "2") (pinfunction "B_2") (pintype "unspecified"))
      (node (ref "R35") (pin "2") (pinfunction "2_2") (pintype "unspecified"))
    )
    (net (code "62") (name "Net-(Q17-E)") (class "Default")
      (node (ref "Q17") (pin "1") (pinfunction "E_1") (pintype "unspecified"))
      (node (ref "Q18") (pin "3") (pinfunction "C_3") (pintype "unspecified"))
    )
    (net (code "63") (name "Net-(Q18-B)") (class "Default")
      (node (ref "Q18") (pin "2") (pinfunction "B_2") (pintype "unspecified"))
      (node (ref "R36") (pin "2") (pinfunction "2_2") (pintype "unspecified"))
    )
    (net (code "64") (name "Net-(Q18-E)") (class "Default")
      (node (ref "Q18") (pin "1") (pinfunction "E_1") (pintype "unspecified"))
      (node (ref "Q19") (pin "3") (pinfunction "C_3") (pintype "unspecified"))
    )
    (net (code "65") (name "Net-(Q19-B)") (class "Default")
      (node (ref "Q19") (pin "2") (pinfunction "B_2") (pintype "unspecified"))
      (node (ref "R37") (pin "2") (pinfunction "2_2") (pintype "unspecified"))
    )
    (net (code "66") (name "Net-(Q19-E)") (class "Default")
      (node (ref "Q19") (pin "1") (pinfunction "E_1") (pintype "unspecified"))
      (node (ref "Q20") (pin "3") (pinfunction "C_3") (pintype "unspecified"))
    )
    (net (code "67") (name "Net-(Q20-B)") (class "Default")
      (node (ref "Q20") (pin "2") (pinfunction "B_2") (pintype "unspecified"))
      (node (ref "R38") (pin "2") (pinfunction "2_2") (pintype "unspecified"))
    )
    (net (code "68") (name "Net-(Q20-E)") (class "Default")
      (node (ref "Q20") (pin "1") (pinfunction "E_1") (pintype "unspecified"))
      (node (ref "Q21") (pin "3") (pinfunction "C_3") (pintype "unspecified"))
    )
    (net (code "69") (name "Net-(Q21-B)") (class "Default")
      (node (ref "Q21") (pin "2") (pinfunction "B_2") (pintype "unspecified"))
      (node (ref "R39") (pin "2") (pinfunction "2_2") (pintype "unspecified"))
    )
    (net (code "70") (name "Net-(Q22-B)") (class "Default")
      (node (ref "Q22") (pin "2") (pinfunction "B_2") (pintype "unspecified"))
      (node (ref "R41") (pin "2") (pinfunction "2_2") (pintype "unspecified"))
    )
    (net (code "71") (name "Net-(Q23-B)") (class "Default")
      (node (ref "Q23") (pin "2") (pinfunction "B_2") (pintype "unspecified"))
      (node (ref "R42") (pin "2") (pinfunction "2_2") (pintype "unspecified"))
    )
    (net (code "72") (name "Net-(Q24-B)") (class "Default")
      (node (ref "Q24") (pin "2") (pinfunction "B_2") (pintype "unspecified"))
      (node (ref "R43") (pin "2") (pinfunction "2_2") (pintype "unspecified"))
    )
    (net (code "73") (name "Net-(R9-Pad2)") (class "Default")
      (node (ref "R9") (pin "2") (pinfunction "2_2") (pintype "unspecified"))
      (node (ref "X") (pin "1") (pinfunction "1_1") (pintype "unspecified"))
    )
    (net (code "74") (name "P") (class "Default")
      (node (ref "D2") (pin "1") (pinfunction "1_1") (pintype "unspecified"))
      (node (ref "R19") (pin "1") (pinfunction "1_1") (pintype "unspecified"))
      (node (ref "R26") (pin "1") (pinfunction "1_1") (pintype "unspecified"))
      (node (ref "R32") (pin "1") (pinfunction "1_1") (pintype "unspecified"))
      (node (ref "R7") (pin "1") (pinfunction "1_1") (pintype "unspecified"))
    )
    (net (code "75") (name "P0") (class "Default")
      (node (ref "J1") (pin "1") (pinfunction "1_1") (pintype "input"))
      (node (ref "P1") (pin "1") (pinfunction "1_1") (pintype "unspecified"))
    )
    (net (code "76") (name "P1") (class "Default")
      (node (ref "J1") (pin "3") (pinfunction "3_3") (pintype "input"))
      (node (ref "P1") (pin "2") (pinfunction "2_2") (pintype "unspecified"))
    )
    (net (code "77") (name "P2") (class "Default")
      (node (ref "J1") (pin "5") (pinfunction "5_5") (pintype "input"))
      (node (ref "P1") (pin "3") (pinfunction "3_3") (pintype "unspecified"))
    )
    (net (code "78") (name "P3") (class "Default")
      (node (ref "J1") (pin "7") (pinfunction "7_7") (pintype "input"))
      (node (ref "P1") (pin "4") (pinfunction "4_4") (pintype "unspecified"))
    )
    (net (code "79") (name "P4") (class "Default")
      (node (ref "J1") (pin "9") (pinfunction "9_9") (pintype "input"))
      (node (ref "P1") (pin "5") (pinfunction "5_5") (pintype "unspecified"))
    )
    (net (code "80") (name "P5") (class "Default")
      (node (ref "J1") (pin "11") (pinfunction "11_11") (pintype "input"))
      (node (ref "P1") (pin "6") (pinfunction "6_6") (pintype "unspecified"))
    )
    (net (code "81") (name "P6") (class "Default")
      (node (ref "J1") (pin "13") (pinfunction "13_13") (pintype "input"))
      (node (ref "P1") (pin "7") (pinfunction "7_7") (pintype "unspecified"))
    )
    (net (code "82") (name "P7") (class "Default")
      (node (ref "J1") (pin "15") (pinfunction "15_15") (pintype "input"))
      (node (ref "P1") (pin "8") (pinfunction "8_8") (pintype "unspecified"))
    )
    (net (code "83") (name "Q") (class "Default")
      (node (ref "D3") (pin "1") (pinfunction "1_1") (pintype "unspecified"))
      (node (ref "R21") (pin "1") (pinfunction "1_1") (pintype "unspecified"))
      (node (ref "R27") (pin "1") (pinfunction "1_1") (pintype "unspecified"))
      (node (ref "R38") (pin "1") (pinfunction "1_1") (pintype "unspecified"))
      (node (ref "R8") (pin "1") (pinfunction "1_1") (pintype "unspecified"))
    )
    (net (code "84") (name "Q0") (class "Default")
      (node (ref "J2") (pin "1") (pinfunction "1_1") (pintype "input"))
      (node (ref "P1") (pin "9") (pinfunction "9_9") (pintype "unspecified"))
    )
    (net (code "85") (name "Q1") (class "Default")
      (node (ref "J2") (pin "3") (pinfunction "3_3") (pintype "input"))
      (node (ref "P1") (pin "10") (pinfunction "10_10") (pintype "unspecified"))
    )
    (net (code "86") (name "Q2") (class "Default")
      (node (ref "J2") (pin "5") (pinfunction "5_5") (pintype "input"))
      (node (ref "P1") (pin "11") (pinfunction "11_11") (pintype "unspecified"))
    )
    (net (code "87") (name "Q3") (class "Default")
      (node (ref "J2") (pin "7") (pinfunction "7_7") (pintype "input"))
      (node (ref "P1") (pin "12") (pinfunction "12_12") (pintype "unspecified"))
    )
    (net (code "88") (name "Q4") (class "Default")
      (node (ref "J2") (pin "9") (pinfunction "9_9") (pintype "input"))
      (node (ref "P1") (pin "13") (pinfunction "13_13") (pintype "unspecified"))
    )
    (net (code "89") (name "Q5") (class "Default")
      (node (ref "J2") (pin "11") (pinfunction "11_11") (pintype "input"))
      (node (ref "P1") (pin "14") (pinfunction "14_14") (pintype "unspecified"))
    )
    (net (code "90") (name "Q6") (class "Default")
      (node (ref "J2") (pin "13") (pinfunction "13_13") (pintype "input"))
      (node (ref "P1") (pin "15") (pinfunction "15_15") (pintype "unspecified"))
    )
    (net (code "91") (name "Q7") (class "Default")
      (node (ref "J2") (pin "15") (pinfunction "15_15") (pintype "input"))
      (node (ref "P1") (pin "16") (pinfunction "16_16") (pintype "unspecified"))
    )
    (net (code "92") (name "X") (class "Default")
      (node (ref "D5") (pin "2") (pinfunction "2_2") (pintype "unspecified"))
      (node (ref "R9") (pin "1") (pinfunction "1_1") (pintype "unspecified"))
    )
    (net (code "93") (name "X0") (class "Default")
      (node (ref "J4") (pin "16") (pinfunction "16_16") (pintype "input"))
      (node (ref "P2") (pin "1") (pinfunction "1_1") (pintype "unspecified"))
    )
    (net (code "94") (name "X1") (class "Default")
      (node (ref "J4") (pin "14") (pinfunction "14_14") (pintype "input"))
      (node (ref "P2") (pin "2") (pinfunction "2_2") (pintype "unspecified"))
    )
    (net (code "95") (name "X2") (class "Default")
      (node (ref "J4") (pin "12") (pinfunction "12_12") (pintype "input"))
      (node (ref "P2") (pin "3") (pinfunction "3_3") (pintype "unspecified"))
    )
    (net (code "96") (name "X3") (class "Default")
      (node (ref "J4") (pin "10") (pinfunction "10_10") (pintype "input"))
      (node (ref "P2") (pin "4") (pinfunction "4_4") (pintype "unspecified"))
    )
    (net (code "97") (name "X4") (class "Default")
      (node (ref "J4") (pin "8") (pinfunction "8_8") (pintype "input"))
      (node (ref "P2") (pin "5") (pinfunction "5_5") (pintype "unspecified"))
    )
    (net (code "98") (name "X5") (class "Default")
      (node (ref "J4") (pin "6") (pinfunction "6_6") (pintype "input"))
      (node (ref "P2") (pin "6") (pinfunction "6_6") (pintype "unspecified"))
    )
    (net (code "99") (name "X6") (class "Default")
      (node (ref "J4") (pin "4") (pinfunction "4_4") (pintype "input"))
      (node (ref "P2") (pin "7") (pinfunction "7_7") (pintype "unspecified"))
    )
    (net (code "100") (name "X7") (class "Default")
      (node (ref "J4") (pin "2") (pinfunction "2_2") (pintype "input"))
      (node (ref "P2") (pin "8") (pinfunction "8_8") (pintype "unspecified"))
    )
  )
)
